# MB_RELAY.net
KiCad netlist of a schematic drawn in Altium Designer
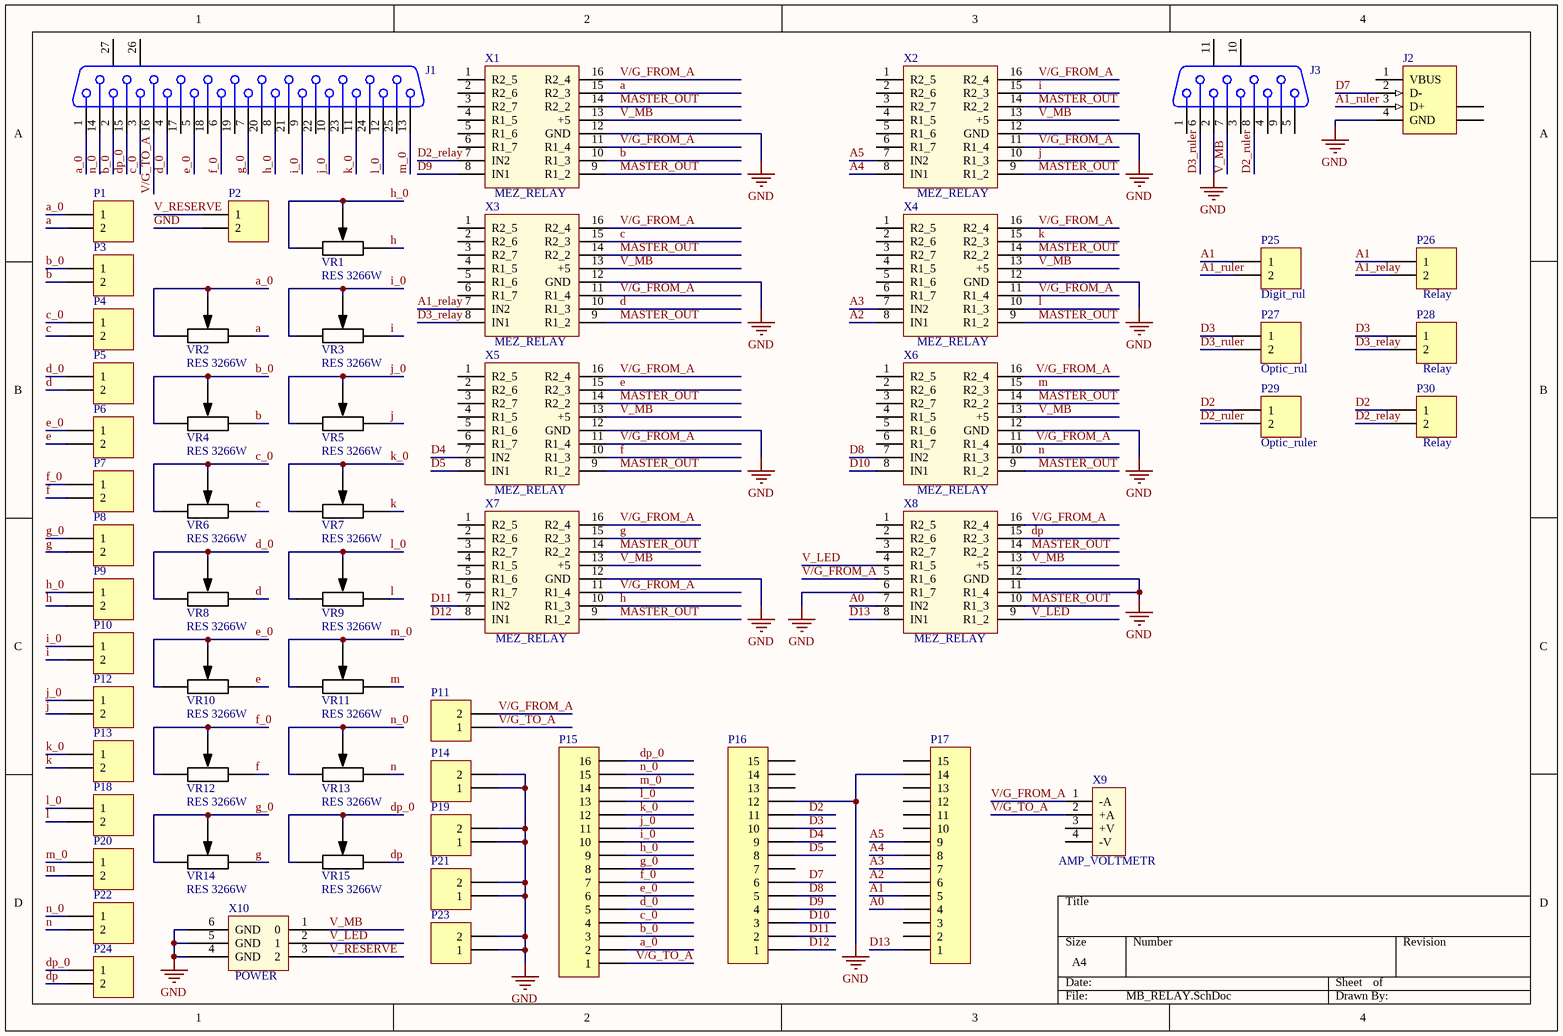
[diagram p0: MB_RELAY.SchDoc]

(export (version "E")
  (design (tool "Eeschema 10.0.6"))
  (components
    (comp (ref "J1")
      (value "D Connector 25")
      (footprint "DSUB1.385-2H25A")
      (description "Receptacle Assembly, 25 Position, Right Angle")
      (fields (field (name "PUBLISHER") "Altium Limited"))
      (libsource (lib "Miscellaneous Connectors") (part "D Connector 25"))
    )
    (comp (ref "J2")
      (value "1-353576-1")
      (footprint "353576")
      (description "USB 1.1, Right Angle, SMT, A Type, Receptacle, 4 Position, White")
      (fields (field (name "PUBLISHER") "Altium Limited"))
      (libsource (lib "AMP Serial Bus USB") (part "1-353576-1"))
    )
    (comp (ref "J3")
      (value "D Connector 9")
      (footprint "DSUB1.385-2H9")
      (description "Receptacle Assembly, 9 Position, Right Angle")
      (fields (field (name "PUBLISHER") "Altium Limited"))
      (libsource (lib "Miscellaneous Connectors") (part "D Connector 9"))
    )
    (comp (ref "P1")
      (value "Header 2")
      (footprint "HDR1X2")
      (description "Header, 2-Pin")
      (fields (field (name "PUBLISHER") "Altium Limited"))
      (libsource (lib "Miscellaneous Connectors") (part "Header 2"))
    )
    (comp (ref "P2")
      (value "Header 2")
      (footprint "HDR1X2")
      (description "Header, 2-Pin")
      (fields (field (name "PUBLISHER") "Altium Limited"))
      (libsource (lib "Miscellaneous Connectors") (part "Header 2"))
    )
    (comp (ref "P3")
      (value "Header 2")
      (footprint "HDR1X2")
      (description "Header, 2-Pin")
      (fields (field (name "PUBLISHER") "Altium Limited"))
      (libsource (lib "Miscellaneous Connectors") (part "Header 2"))
    )
    (comp (ref "P4")
      (value "Header 2")
      (footprint "HDR1X2")
      (description "Header, 2-Pin")
      (fields (field (name "PUBLISHER") "Altium Limited"))
      (libsource (lib "Miscellaneous Connectors") (part "Header 2"))
    )
    (comp (ref "P5")
      (value "Header 2")
      (footprint "HDR1X2")
      (description "Header, 2-Pin")
      (fields (field (name "PUBLISHER") "Altium Limited"))
      (libsource (lib "Miscellaneous Connectors") (part "Header 2"))
    )
    (comp (ref "P6")
      (value "GND")
      (footprint "HDR1X2")
      (description "Header, 2-Pin")
      (fields (field (name "PUBLISHER") "Altium Limited"))
      (libsource (lib "Miscellaneous Connectors") (part "Header 2"))
    )
    (comp (ref "P7")
      (value "GND")
      (footprint "HDR1X2")
      (description "Header, 2-Pin")
      (fields (field (name "PUBLISHER") "Altium Limited"))
      (libsource (lib "Miscellaneous Connectors") (part "Header 2"))
    )
    (comp (ref "P8")
      (value "GND")
      (footprint "HDR1X2")
      (description "Header, 2-Pin")
      (fields (field (name "PUBLISHER") "Altium Limited"))
      (libsource (lib "Miscellaneous Connectors") (part "Header 2"))
    )
    (comp (ref "P9")
      (value "GND")
      (footprint "HDR1X2")
      (description "Header, 2-Pin")
      (fields (field (name "PUBLISHER") "Altium Limited"))
      (libsource (lib "Miscellaneous Connectors") (part "Header 2"))
    )
    (comp (ref "P10")
      (value "Header 2")
      (footprint "HDR1X2")
      (description "Header, 2-Pin")
      (fields (field (name "PUBLISHER") "Altium Limited"))
      (libsource (lib "Miscellaneous Connectors") (part "Header 2"))
    )
    (comp (ref "P11")
      (value "Header 2")
      (footprint "HDR1X2")
      (description "Header, 2-Pin")
      (fields (field (name "PUBLISHER") "Altium Limited"))
      (libsource (lib "") (part "Header 2_1"))
    )
    (comp (ref "P12")
      (value "Header 2")
      (footprint "HDR1X2")
      (description "Header, 2-Pin")
      (fields (field (name "PUBLISHER") "Altium Limited"))
      (libsource (lib "Miscellaneous Connectors") (part "Header 2"))
    )
    (comp (ref "P13")
      (value "GND")
      (footprint "HDR1X2")
      (description "Header, 2-Pin")
      (fields (field (name "PUBLISHER") "Altium Limited"))
      (libsource (lib "Miscellaneous Connectors") (part "Header 2"))
    )
    (comp (ref "P14")
      (value "GND")
      (footprint "HDR1X2")
      (description "Header, 2-Pin")
      (fields (field (name "PUBLISHER") "Altium Limited"))
      (libsource (lib "") (part "Header 2_1"))
    )
    (comp (ref "P15")
      (value "Header 16")
      (footprint "HDR1X16")
      (description "Header, 16-Pin")
      (fields (field (name "PUBLISHER") "Altium Limited"))
      (libsource (lib "Miscellaneous Connectors") (part "Header 16"))
    )
    (comp (ref "P16")
      (value "Header 15")
      (footprint "HDR1X15")
      (description "Header, 15-Pin")
      (fields (field (name "PUBLISHER") "Altium Limited"))
      (libsource (lib "") (part "Header 15_1"))
    )
    (comp (ref "P17")
      (value "Header 15")
      (footprint "HDR1X15")
      (description "Header, 15-Pin")
      (fields (field (name "PUBLISHER") "Altium Limited"))
      (libsource (lib "Miscellaneous Connectors") (part "Header 15"))
    )
    (comp (ref "P18")
      (value "GND")
      (footprint "HDR1X2")
      (description "Header, 2-Pin")
      (fields (field (name "PUBLISHER") "Altium Limited"))
      (libsource (lib "Miscellaneous Connectors") (part "Header 2"))
    )
    (comp (ref "P19")
      (value "GND")
      (footprint "HDR1X2")
      (description "Header, 2-Pin")
      (fields (field (name "PUBLISHER") "Altium Limited"))
      (libsource (lib "") (part "Header 2_1"))
    )
    (comp (ref "P20")
      (value "GND")
      (footprint "HDR1X2")
      (description "Header, 2-Pin")
      (fields (field (name "PUBLISHER") "Altium Limited"))
      (libsource (lib "Miscellaneous Connectors") (part "Header 2"))
    )
    (comp (ref "P21")
      (value "GND")
      (footprint "HDR1X2")
      (description "Header, 2-Pin")
      (fields (field (name "PUBLISHER") "Altium Limited"))
      (libsource (lib "") (part "Header 2_1"))
    )
    (comp (ref "P22")
      (value "GND")
      (footprint "HDR1X2")
      (description "Header, 2-Pin")
      (fields (field (name "PUBLISHER") "Altium Limited"))
      (libsource (lib "Miscellaneous Connectors") (part "Header 2"))
    )
    (comp (ref "P23")
      (value "GND")
      (footprint "HDR1X2")
      (description "Header, 2-Pin")
      (fields (field (name "PUBLISHER") "Altium Limited"))
      (libsource (lib "") (part "Header 2_1"))
    )
    (comp (ref "P24")
      (value "GND")
      (footprint "HDR1X2")
      (description "Header, 2-Pin")
      (fields (field (name "PUBLISHER") "Altium Limited"))
      (libsource (lib "Miscellaneous Connectors") (part "Header 2"))
    )
    (comp (ref "P25")
      (value "Digit_rul")
      (footprint "HDR1X2")
      (description "Header, 2-Pin")
      (fields (field (name "PUBLISHER") "Altium Limited"))
      (libsource (lib "Miscellaneous Connectors") (part "Header 2"))
    )
    (comp (ref "P26")
      (value "Relay")
      (footprint "HDR1X2")
      (description "Header, 2-Pin")
      (fields (field (name "PUBLISHER") "Altium Limited"))
      (libsource (lib "Miscellaneous Connectors") (part "Header 2"))
    )
    (comp (ref "P27")
      (value "Optic_rul")
      (footprint "HDR1X2")
      (description "Header, 2-Pin")
      (fields (field (name "PUBLISHER") "Altium Limited"))
      (libsource (lib "Miscellaneous Connectors") (part "Header 2"))
    )
    (comp (ref "P28")
      (value "Relay")
      (footprint "HDR1X2")
      (description "Header, 2-Pin")
      (fields (field (name "PUBLISHER") "Altium Limited"))
      (libsource (lib "Miscellaneous Connectors") (part "Header 2"))
    )
    (comp (ref "P29")
      (value "Optic_ruler")
      (footprint "HDR1X2")
      (description "Header, 2-Pin")
      (fields (field (name "PUBLISHER") "Altium Limited"))
      (libsource (lib "Miscellaneous Connectors") (part "Header 2"))
    )
    (comp (ref "P30")
      (value "Relay")
      (footprint "HDR1X2")
      (description "Header, 2-Pin")
      (fields (field (name "PUBLISHER") "Altium Limited"))
      (libsource (lib "Miscellaneous Connectors") (part "Header 2"))
    )
    (comp (ref "VR1")
      (value "RES 3266W")
      (footprint "aab_Passive:RES 3266W")
      (libsource (lib "aab_Schlib") (part "RES 3266W"))
    )
    (comp (ref "VR2")
      (value "RES 3266W")
      (footprint "aab_Passive:RES 3266W")
      (libsource (lib "aab_Schlib") (part "RES 3266W"))
    )
    (comp (ref "VR3")
      (value "RES 3266W")
      (footprint "aab_Passive:RES 3266W")
      (libsource (lib "aab_Schlib") (part "RES 3266W"))
    )
    (comp (ref "VR4")
      (value "RES 3266W")
      (footprint "aab_Passive:RES 3266W")
      (libsource (lib "aab_Schlib") (part "RES 3266W"))
    )
    (comp (ref "VR5")
      (value "RES 3266W")
      (footprint "aab_Passive:RES 3266W")
      (libsource (lib "aab_Schlib") (part "RES 3266W"))
    )
    (comp (ref "VR6")
      (value "RES 3266W")
      (footprint "aab_Passive:RES 3266W")
      (libsource (lib "aab_Schlib") (part "RES 3266W"))
    )
    (comp (ref "VR7")
      (value "RES 3266W")
      (footprint "aab_Passive:RES 3266W")
      (libsource (lib "aab_Schlib") (part "RES 3266W"))
    )
    (comp (ref "VR8")
      (value "RES 3266W")
      (footprint "aab_Passive:RES 3266W")
      (libsource (lib "aab_Schlib") (part "RES 3266W"))
    )
    (comp (ref "VR9")
      (value "RES 3266W")
      (footprint "aab_Passive:RES 3266W")
      (libsource (lib "aab_Schlib") (part "RES 3266W"))
    )
    (comp (ref "VR10")
      (value "RES 3266W")
      (footprint "aab_Passive:RES 3266W")
      (libsource (lib "aab_Schlib") (part "RES 3266W"))
    )
    (comp (ref "VR11")
      (value "RES 3266W")
      (footprint "aab_Passive:RES 3266W")
      (libsource (lib "aab_Schlib") (part "RES 3266W"))
    )
    (comp (ref "VR12")
      (value "RES 3266W")
      (footprint "aab_Passive:RES 3266W")
      (libsource (lib "aab_Schlib") (part "RES 3266W"))
    )
    (comp (ref "VR13")
      (value "RES 3266W")
      (footprint "aab_Passive:RES 3266W")
      (libsource (lib "aab_Schlib") (part "RES 3266W"))
    )
    (comp (ref "VR14")
      (value "RES 3266W")
      (footprint "aab_Passive:RES 3266W")
      (libsource (lib "aab_Schlib") (part "RES 3266W"))
    )
    (comp (ref "VR15")
      (value "RES 3266W")
      (footprint "aab_Passive:RES 3266W")
      (libsource (lib "aab_Schlib") (part "RES 3266W"))
    )
    (comp (ref "X1")
      (value "MEZ_RELAY")
      (footprint "MEZ_RELAY")
      (libsource (lib "msp_SchLib") (part "MEZ_RELAY"))
    )
    (comp (ref "X2")
      (value "MEZ_RELAY")
      (footprint "MEZ_RELAY")
      (libsource (lib "msp_SchLib") (part "MEZ_RELAY"))
    )
    (comp (ref "X3")
      (value "MEZ_RELAY")
      (footprint "MEZ_RELAY")
      (libsource (lib "msp_SchLib") (part "MEZ_RELAY"))
    )
    (comp (ref "X4")
      (value "MEZ_RELAY")
      (footprint "MEZ_RELAY")
      (libsource (lib "msp_SchLib") (part "MEZ_RELAY"))
    )
    (comp (ref "X5")
      (value "MEZ_RELAY")
      (footprint "MEZ_RELAY")
      (libsource (lib "msp_SchLib") (part "MEZ_RELAY"))
    )
    (comp (ref "X6")
      (value "MEZ_RELAY")
      (footprint "MEZ_RELAY")
      (libsource (lib "msp_SchLib") (part "MEZ_RELAY"))
    )
    (comp (ref "X7")
      (value "MEZ_RELAY")
      (footprint "MEZ_RELAY")
      (libsource (lib "msp_SchLib") (part "MEZ_RELAY"))
    )
    (comp (ref "X8")
      (value "MEZ_RELAY")
      (footprint "MEZ_RELAY")
      (libsource (lib "msp_SchLib") (part "MEZ_RELAY"))
    )
    (comp (ref "X9")
      (value "AMP_VOLTMETR")
      (footprint "vpl_Passive:AMP_VOLTMETER")
      (libsource (lib "msp_SchLib") (part "AMP_VOLTMETR"))
    )
    (comp (ref "X10")
      (value "POWER")
      (footprint "vpl_Passive:POWER")
      (libsource (lib "msp_SchLib") (part "POWER"))
    )
  )
  (nets
    (net (code "1") (name "/A0") (class "Default")
      (node (ref "P17") (pin "4") (pinfunction "4_4") (pintype "passive"))
      (node (ref "X8") (pin "7") (pinfunction "IN2_7") (pintype "passive"))
    )
    (net (code "2") (name "/A1") (class "Default")
      (node (ref "P17") (pin "5") (pinfunction "5_5") (pintype "passive"))
      (node (ref "P25") (pin "1") (pinfunction "1_1") (pintype "passive"))
      (node (ref "P26") (pin "1") (pinfunction "1_1") (pintype "passive"))
    )
    (net (code "3") (name "/A1_relay") (class "Default")
      (node (ref "P26") (pin "2") (pinfunction "2_2") (pintype "passive"))
      (node (ref "X3") (pin "7") (pinfunction "IN2_7") (pintype "passive"))
    )
    (net (code "4") (name "/A1_ruler") (class "Default")
      (node (ref "J2") (pin "3") (pinfunction "D+_3") (pintype "input"))
      (node (ref "P25") (pin "2") (pinfunction "2_2") (pintype "passive"))
    )
    (net (code "5") (name "/A2") (class "Default")
      (node (ref "P17") (pin "6") (pinfunction "6_6") (pintype "passive"))
      (node (ref "X4") (pin "8") (pinfunction "IN1_8") (pintype "passive"))
    )
    (net (code "6") (name "/A3") (class "Default")
      (node (ref "P17") (pin "7") (pinfunction "7_7") (pintype "passive"))
      (node (ref "X4") (pin "7") (pinfunction "IN2_7") (pintype "passive"))
    )
    (net (code "7") (name "/A4") (class "Default")
      (node (ref "P17") (pin "8") (pinfunction "8_8") (pintype "passive"))
      (node (ref "X2") (pin "8") (pinfunction "IN1_8") (pintype "passive"))
    )
    (net (code "8") (name "/A5") (class "Default")
      (node (ref "P17") (pin "9") (pinfunction "9_9") (pintype "passive"))
      (node (ref "X2") (pin "7") (pinfunction "IN2_7") (pintype "passive"))
    )
    (net (code "9") (name "/D2") (class "Default")
      (node (ref "P16") (pin "11") (pinfunction "11_11") (pintype "passive"))
      (node (ref "P29") (pin "1") (pinfunction "1_1") (pintype "passive"))
      (node (ref "P30") (pin "1") (pinfunction "1_1") (pintype "passive"))
    )
    (net (code "10") (name "/D2_relay") (class "Default")
      (node (ref "P30") (pin "2") (pinfunction "2_2") (pintype "passive"))
      (node (ref "X1") (pin "7") (pinfunction "IN2_7") (pintype "passive"))
    )
    (net (code "11") (name "/D2_ruler") (class "Default")
      (node (ref "J3") (pin "8") (pinfunction "8_8") (pintype "passive"))
      (node (ref "P29") (pin "2") (pinfunction "2_2") (pintype "passive"))
    )
    (net (code "12") (name "/D3") (class "Default")
      (node (ref "P16") (pin "10") (pinfunction "10_10") (pintype "passive"))
      (node (ref "P27") (pin "1") (pinfunction "1_1") (pintype "passive"))
      (node (ref "P28") (pin "1") (pinfunction "1_1") (pintype "passive"))
    )
    (net (code "13") (name "/D3_relay") (class "Default")
      (node (ref "P28") (pin "2") (pinfunction "2_2") (pintype "passive"))
      (node (ref "X3") (pin "8") (pinfunction "IN1_8") (pintype "passive"))
    )
    (net (code "14") (name "/D3_ruler") (class "Default")
      (node (ref "J3") (pin "6") (pinfunction "6_6") (pintype "passive"))
      (node (ref "P27") (pin "2") (pinfunction "2_2") (pintype "passive"))
    )
    (net (code "15") (name "/D4") (class "Default")
      (node (ref "P16") (pin "9") (pinfunction "9_9") (pintype "passive"))
      (node (ref "X5") (pin "7") (pinfunction "IN2_7") (pintype "passive"))
    )
    (net (code "16") (name "/D5") (class "Default")
      (node (ref "P16") (pin "8") (pinfunction "8_8") (pintype "passive"))
      (node (ref "X5") (pin "8") (pinfunction "IN1_8") (pintype "passive"))
    )
    (net (code "17") (name "/D7") (class "Default")
      (node (ref "J2") (pin "2") (pinfunction "D-_2") (pintype "input"))
      (node (ref "P16") (pin "6") (pinfunction "6_6") (pintype "passive"))
    )
    (net (code "18") (name "/D8") (class "Default")
      (node (ref "P16") (pin "5") (pinfunction "5_5") (pintype "passive"))
      (node (ref "X6") (pin "7") (pinfunction "IN2_7") (pintype "passive"))
    )
    (net (code "19") (name "/D9") (class "Default")
      (node (ref "P16") (pin "4") (pinfunction "4_4") (pintype "passive"))
      (node (ref "X1") (pin "8") (pinfunction "IN1_8") (pintype "passive"))
    )
    (net (code "20") (name "/D10") (class "Default")
      (node (ref "P16") (pin "3") (pinfunction "3_3") (pintype "passive"))
      (node (ref "X6") (pin "8") (pinfunction "IN1_8") (pintype "passive"))
    )
    (net (code "21") (name "/D11") (class "Default")
      (node (ref "P16") (pin "2") (pinfunction "2_2") (pintype "passive"))
      (node (ref "X7") (pin "7") (pinfunction "IN2_7") (pintype "passive"))
    )
    (net (code "22") (name "/D12") (class "Default")
      (node (ref "P16") (pin "1") (pinfunction "1_1") (pintype "passive"))
      (node (ref "X7") (pin "8") (pinfunction "IN1_8") (pintype "passive"))
    )
    (net (code "23") (name "/D13") (class "Default")
      (node (ref "P17") (pin "1") (pinfunction "1_1") (pintype "passive"))
      (node (ref "X8") (pin "8") (pinfunction "IN1_8") (pintype "passive"))
    )
    (net (code "24") (name "/MASTER_OUT") (class "Default")
      (node (ref "X1") (pin "14") (pinfunction "R2_2_14") (pintype "passive"))
      (node (ref "X1") (pin "9") (pinfunction "R1_2_9") (pintype "passive"))
      (node (ref "X2") (pin "14") (pinfunction "R2_2_14") (pintype "passive"))
      (node (ref "X2") (pin "9") (pinfunction "R1_2_9") (pintype "passive"))
      (node (ref "X3") (pin "14") (pinfunction "R2_2_14") (pintype "passive"))
      (node (ref "X3") (pin "9") (pinfunction "R1_2_9") (pintype "passive"))
      (node (ref "X4") (pin "14") (pinfunction "R2_2_14") (pintype "passive"))
      (node (ref "X4") (pin "9") (pinfunction "R1_2_9") (pintype "passive"))
      (node (ref "X5") (pin "14") (pinfunction "R2_2_14") (pintype "passive"))
      (node (ref "X5") (pin "9") (pinfunction "R1_2_9") (pintype "passive"))
      (node (ref "X6") (pin "14") (pinfunction "R2_2_14") (pintype "passive"))
      (node (ref "X6") (pin "9") (pinfunction "R1_2_9") (pintype "passive"))
      (node (ref "X7") (pin "14") (pinfunction "R2_2_14") (pintype "passive"))
      (node (ref "X7") (pin "9") (pinfunction "R1_2_9") (pintype "passive"))
      (node (ref "X8") (pin "10") (pinfunction "R1_3_10") (pintype "passive"))
      (node (ref "X8") (pin "14") (pinfunction "R2_2_14") (pintype "passive"))
    )
    (net (code "25") (name "/V_LED") (class "Default")
      (node (ref "X10") (pin "2") (pinfunction "1_2") (pintype "passive"))
      (node (ref "X8") (pin "4") (pinfunction "R1_5_4") (pintype "passive"))
      (node (ref "X8") (pin "9") (pinfunction "R1_2_9") (pintype "passive"))
    )
    (net (code "26") (name "/V_MB") (class "Default")
      (node (ref "J3") (pin "7") (pinfunction "7_7") (pintype "passive"))
      (node (ref "X1") (pin "13") (pinfunction "+5_13") (pintype "passive"))
      (node (ref "X10") (pin "1") (pinfunction "0_1") (pintype "passive"))
      (node (ref "X2") (pin "13") (pinfunction "+5_13") (pintype "passive"))
      (node (ref "X3") (pin "13") (pinfunction "+5_13") (pintype "passive"))
      (node (ref "X4") (pin "13") (pinfunction "+5_13") (pintype "passive"))
      (node (ref "X5") (pin "13") (pinfunction "+5_13") (pintype "passive"))
      (node (ref "X6") (pin "13") (pinfunction "+5_13") (pintype "passive"))
      (node (ref "X7") (pin "13") (pinfunction "+5_13") (pintype "passive"))
      (node (ref "X8") (pin "13") (pinfunction "+5_13") (pintype "passive"))
    )
    (net (code "27") (name "/V_RESERVE") (class "Default")
      (node (ref "P2") (pin "1") (pinfunction "1_1") (pintype "passive"))
      (node (ref "X10") (pin "3") (pinfunction "2_3") (pintype "passive"))
    )
    (net (code "28") (name "/V{slash}G_FROM_A") (class "Default")
      (node (ref "P11") (pin "2") (pinfunction "2_2") (pintype "passive"))
      (node (ref "X1") (pin "11") (pinfunction "R1_4_11") (pintype "passive"))
      (node (ref "X1") (pin "16") (pinfunction "R2_4_16") (pintype "passive"))
      (node (ref "X2") (pin "11") (pinfunction "R1_4_11") (pintype "passive"))
      (node (ref "X2") (pin "16") (pinfunction "R2_4_16") (pintype "passive"))
      (node (ref "X3") (pin "11") (pinfunction "R1_4_11") (pintype "passive"))
      (node (ref "X3") (pin "16") (pinfunction "R2_4_16") (pintype "passive"))
      (node (ref "X4") (pin "11") (pinfunction "R1_4_11") (pintype "passive"))
      (node (ref "X4") (pin "16") (pinfunction "R2_4_16") (pintype "passive"))
      (node (ref "X5") (pin "11") (pinfunction "R1_4_11") (pintype "passive"))
      (node (ref "X5") (pin "16") (pinfunction "R2_4_16") (pintype "passive"))
      (node (ref "X6") (pin "11") (pinfunction "R1_4_11") (pintype "passive"))
      (node (ref "X6") (pin "16") (pinfunction "R2_4_16") (pintype "passive"))
      (node (ref "X7") (pin "11") (pinfunction "R1_4_11") (pintype "passive"))
      (node (ref "X7") (pin "16") (pinfunction "R2_4_16") (pintype "passive"))
      (node (ref "X8") (pin "16") (pinfunction "R2_4_16") (pintype "passive"))
      (node (ref "X8") (pin "5") (pinfunction "R1_6_5") (pintype "passive"))
      (node (ref "X9") (pin "1") (pinfunction "-A_1") (pintype "passive"))
    )
    (net (code "29") (name "/V{slash}G_TO_A") (class "Default")
      (node (ref "J1") (pin "16") (pinfunction "16_16") (pintype "passive"))
      (node (ref "P11") (pin "1") (pinfunction "1_1") (pintype "passive"))
      (node (ref "P15") (pin "1") (pinfunction "1_1") (pintype "passive"))
      (node (ref "X9") (pin "2") (pinfunction "+A_2") (pintype "passive"))
    )
    (net (code "30") (name "/a") (class "Default")
      (node (ref "P1") (pin "2") (pinfunction "2_2") (pintype "passive"))
      (node (ref "VR2") (pin "3") (pinfunction "3_3") (pintype "passive"))
      (node (ref "X1") (pin "15") (pinfunction "R2_3_15") (pintype "passive"))
    )
    (net (code "31") (name "/a_0") (class "Default")
      (node (ref "J1") (pin "1") (pinfunction "1_1") (pintype "passive"))
      (node (ref "P1") (pin "1") (pinfunction "1_1") (pintype "passive"))
      (node (ref "P15") (pin "2") (pinfunction "2_2") (pintype "passive"))
      (node (ref "VR2") (pin "1") (pinfunction "1_1") (pintype "passive"))
      (node (ref "VR2") (pin "2") (pinfunction "2_2") (pintype "passive"))
    )
    (net (code "32") (name "/b") (class "Default")
      (node (ref "P3") (pin "2") (pinfunction "2_2") (pintype "passive"))
      (node (ref "VR4") (pin "3") (pinfunction "3_3") (pintype "passive"))
      (node (ref "X1") (pin "10") (pinfunction "R1_3_10") (pintype "passive"))
    )
    (net (code "33") (name "/b_0") (class "Default")
      (node (ref "J1") (pin "2") (pinfunction "2_2") (pintype "passive"))
      (node (ref "P15") (pin "3") (pinfunction "3_3") (pintype "passive"))
      (node (ref "P3") (pin "1") (pinfunction "1_1") (pintype "passive"))
      (node (ref "VR4") (pin "1") (pinfunction "1_1") (pintype "passive"))
      (node (ref "VR4") (pin "2") (pinfunction "2_2") (pintype "passive"))
    )
    (net (code "34") (name "/c") (class "Default")
      (node (ref "P4") (pin "2") (pinfunction "2_2") (pintype "passive"))
      (node (ref "VR6") (pin "3") (pinfunction "3_3") (pintype "passive"))
      (node (ref "X3") (pin "15") (pinfunction "R2_3_15") (pintype "passive"))
    )
    (net (code "35") (name "/c_0") (class "Default")
      (node (ref "J1") (pin "3") (pinfunction "3_3") (pintype "passive"))
      (node (ref "P15") (pin "4") (pinfunction "4_4") (pintype "passive"))
      (node (ref "P4") (pin "1") (pinfunction "1_1") (pintype "passive"))
      (node (ref "VR6") (pin "1") (pinfunction "1_1") (pintype "passive"))
      (node (ref "VR6") (pin "2") (pinfunction "2_2") (pintype "passive"))
    )
    (net (code "36") (name "/d") (class "Default")
      (node (ref "P5") (pin "2") (pinfunction "2_2") (pintype "passive"))
      (node (ref "VR8") (pin "3") (pinfunction "3_3") (pintype "passive"))
      (node (ref "X3") (pin "10") (pinfunction "R1_3_10") (pintype "passive"))
    )
    (net (code "37") (name "/d_0") (class "Default")
      (node (ref "J1") (pin "4") (pinfunction "4_4") (pintype "passive"))
      (node (ref "P15") (pin "5") (pinfunction "5_5") (pintype "passive"))
      (node (ref "P5") (pin "1") (pinfunction "1_1") (pintype "passive"))
      (node (ref "VR8") (pin "1") (pinfunction "1_1") (pintype "passive"))
      (node (ref "VR8") (pin "2") (pinfunction "2_2") (pintype "passive"))
    )
    (net (code "38") (name "/dp") (class "Default")
      (node (ref "P24") (pin "2") (pinfunction "2_2") (pintype "passive"))
      (node (ref "VR15") (pin "3") (pinfunction "3_3") (pintype "passive"))
      (node (ref "X8") (pin "15") (pinfunction "R2_3_15") (pintype "passive"))
    )
    (net (code "39") (name "/dp_0") (class "Default")
      (node (ref "J1") (pin "15") (pinfunction "15_15") (pintype "passive"))
      (node (ref "P15") (pin "16") (pinfunction "16_16") (pintype "passive"))
      (node (ref "P24") (pin "1") (pinfunction "1_1") (pintype "passive"))
      (node (ref "VR15") (pin "1") (pinfunction "1_1") (pintype "passive"))
      (node (ref "VR15") (pin "2") (pinfunction "2_2") (pintype "passive"))
    )
    (net (code "40") (name "/e") (class "Default")
      (node (ref "P6") (pin "2") (pinfunction "2_2") (pintype "passive"))
      (node (ref "VR10") (pin "3") (pinfunction "3_3") (pintype "passive"))
      (node (ref "X5") (pin "15") (pinfunction "R2_3_15") (pintype "passive"))
    )
    (net (code "41") (name "/e_0") (class "Default")
      (node (ref "J1") (pin "5") (pinfunction "5_5") (pintype "passive"))
      (node (ref "P15") (pin "6") (pinfunction "6_6") (pintype "passive"))
      (node (ref "P6") (pin "1") (pinfunction "1_1") (pintype "passive"))
      (node (ref "VR10") (pin "1") (pinfunction "1_1") (pintype "passive"))
      (node (ref "VR10") (pin "2") (pinfunction "2_2") (pintype "passive"))
    )
    (net (code "42") (name "/f") (class "Default")
      (node (ref "P7") (pin "2") (pinfunction "2_2") (pintype "passive"))
      (node (ref "VR12") (pin "3") (pinfunction "3_3") (pintype "passive"))
      (node (ref "X5") (pin "10") (pinfunction "R1_3_10") (pintype "passive"))
    )
    (net (code "43") (name "/f_0") (class "Default")
      (node (ref "J1") (pin "6") (pinfunction "6_6") (pintype "passive"))
      (node (ref "P15") (pin "7") (pinfunction "7_7") (pintype "passive"))
      (node (ref "P7") (pin "1") (pinfunction "1_1") (pintype "passive"))
      (node (ref "VR12") (pin "1") (pinfunction "1_1") (pintype "passive"))
      (node (ref "VR12") (pin "2") (pinfunction "2_2") (pintype "passive"))
    )
    (net (code "44") (name "/g") (class "Default")
      (node (ref "P8") (pin "2") (pinfunction "2_2") (pintype "passive"))
      (node (ref "VR14") (pin "3") (pinfunction "3_3") (pintype "passive"))
      (node (ref "X7") (pin "15") (pinfunction "R2_3_15") (pintype "passive"))
    )
    (net (code "45") (name "/g_0") (class "Default")
      (node (ref "J1") (pin "7") (pinfunction "7_7") (pintype "passive"))
      (node (ref "P15") (pin "8") (pinfunction "8_8") (pintype "passive"))
      (node (ref "P8") (pin "1") (pinfunction "1_1") (pintype "passive"))
      (node (ref "VR14") (pin "1") (pinfunction "1_1") (pintype "passive"))
      (node (ref "VR14") (pin "2") (pinfunction "2_2") (pintype "passive"))
    )
    (net (code "46") (name "/h") (class "Default")
      (node (ref "P9") (pin "2") (pinfunction "2_2") (pintype "passive"))
      (node (ref "VR1") (pin "3") (pinfunction "3_3") (pintype "passive"))
      (node (ref "X7") (pin "10") (pinfunction "R1_3_10") (pintype "passive"))
    )
    (net (code "47") (name "/h_0") (class "Default")
      (node (ref "J1") (pin "8") (pinfunction "8_8") (pintype "passive"))
      (node (ref "P15") (pin "9") (pinfunction "9_9") (pintype "passive"))
      (node (ref "P9") (pin "1") (pinfunction "1_1") (pintype "passive"))
      (node (ref "VR1") (pin "1") (pinfunction "1_1") (pintype "passive"))
      (node (ref "VR1") (pin "2") (pinfunction "2_2") (pintype "passive"))
    )
    (net (code "48") (name "/i") (class "Default")
      (node (ref "P10") (pin "2") (pinfunction "2_2") (pintype "passive"))
      (node (ref "VR3") (pin "3") (pinfunction "3_3") (pintype "passive"))
      (node (ref "X2") (pin "15") (pinfunction "R2_3_15") (pintype "passive"))
    )
    (net (code "49") (name "/i_0") (class "Default")
      (node (ref "J1") (pin "9") (pinfunction "9_9") (pintype "passive"))
      (node (ref "P10") (pin "1") (pinfunction "1_1") (pintype "passive"))
      (node (ref "P15") (pin "10") (pinfunction "10_10") (pintype "passive"))
      (node (ref "VR3") (pin "1") (pinfunction "1_1") (pintype "passive"))
      (node (ref "VR3") (pin "2") (pinfunction "2_2") (pintype "passive"))
    )
    (net (code "50") (name "/j") (class "Default")
      (node (ref "P12") (pin "2") (pinfunction "2_2") (pintype "passive"))
      (node (ref "VR5") (pin "3") (pinfunction "3_3") (pintype "passive"))
      (node (ref "X2") (pin "10") (pinfunction "R1_3_10") (pintype "passive"))
    )
    (net (code "51") (name "/j_0") (class "Default")
      (node (ref "J1") (pin "10") (pinfunction "10_10") (pintype "passive"))
      (node (ref "P12") (pin "1") (pinfunction "1_1") (pintype "passive"))
      (node (ref "P15") (pin "11") (pinfunction "11_11") (pintype "passive"))
      (node (ref "VR5") (pin "1") (pinfunction "1_1") (pintype "passive"))
      (node (ref "VR5") (pin "2") (pinfunction "2_2") (pintype "passive"))
    )
    (net (code "52") (name "/k") (class "Default")
      (node (ref "P13") (pin "2") (pinfunction "2_2") (pintype "passive"))
      (node (ref "VR7") (pin "3") (pinfunction "3_3") (pintype "passive"))
      (node (ref "X4") (pin "15") (pinfunction "R2_3_15") (pintype "passive"))
    )
    (net (code "53") (name "/k_0") (class "Default")
      (node (ref "J1") (pin "11") (pinfunction "11_11") (pintype "passive"))
      (node (ref "P13") (pin "1") (pinfunction "1_1") (pintype "passive"))
      (node (ref "P15") (pin "12") (pinfunction "12_12") (pintype "passive"))
      (node (ref "VR7") (pin "1") (pinfunction "1_1") (pintype "passive"))
      (node (ref "VR7") (pin "2") (pinfunction "2_2") (pintype "passive"))
    )
    (net (code "54") (name "/l") (class "Default")
      (node (ref "P18") (pin "2") (pinfunction "2_2") (pintype "passive"))
      (node (ref "VR9") (pin "3") (pinfunction "3_3") (pintype "passive"))
      (node (ref "X4") (pin "10") (pinfunction "R1_3_10") (pintype "passive"))
    )
    (net (code "55") (name "/l_0") (class "Default")
      (node (ref "J1") (pin "12") (pinfunction "12_12") (pintype "passive"))
      (node (ref "P15") (pin "13") (pinfunction "13_13") (pintype "passive"))
      (node (ref "P18") (pin "1") (pinfunction "1_1") (pintype "passive"))
      (node (ref "VR9") (pin "1") (pinfunction "1_1") (pintype "passive"))
      (node (ref "VR9") (pin "2") (pinfunction "2_2") (pintype "passive"))
    )
    (net (code "56") (name "/m") (class "Default")
      (node (ref "P20") (pin "2") (pinfunction "2_2") (pintype "passive"))
      (node (ref "VR11") (pin "3") (pinfunction "3_3") (pintype "passive"))
      (node (ref "X6") (pin "15") (pinfunction "R2_3_15") (pintype "passive"))
    )
    (net (code "57") (name "/m_0") (class "Default")
      (node (ref "J1") (pin "13") (pinfunction "13_13") (pintype "passive"))
      (node (ref "P15") (pin "14") (pinfunction "14_14") (pintype "passive"))
      (node (ref "P20") (pin "1") (pinfunction "1_1") (pintype "passive"))
      (node (ref "VR11") (pin "1") (pinfunction "1_1") (pintype "passive"))
      (node (ref "VR11") (pin "2") (pinfunction "2_2") (pintype "passive"))
    )
    (net (code "58") (name "/n") (class "Default")
      (node (ref "P22") (pin "2") (pinfunction "2_2") (pintype "passive"))
      (node (ref "VR13") (pin "3") (pinfunction "3_3") (pintype "passive"))
      (node (ref "X6") (pin "10") (pinfunction "R1_3_10") (pintype "passive"))
    )
    (net (code "59") (name "/n_0") (class "Default")
      (node (ref "J1") (pin "14") (pinfunction "14_14") (pintype "passive"))
      (node (ref "P15") (pin "15") (pinfunction "15_15") (pintype "passive"))
      (node (ref "P22") (pin "1") (pinfunction "1_1") (pintype "passive"))
      (node (ref "VR13") (pin "1") (pinfunction "1_1") (pintype "passive"))
      (node (ref "VR13") (pin "2") (pinfunction "2_2") (pintype "passive"))
    )
    (net (code "60") (name "GND") (class "Default")
      (node (ref "J2") (pin "4") (pinfunction "GND_4") (pintype "power_in"))
      (node (ref "J3") (pin "2") (pinfunction "2_2") (pintype "passive"))
      (node (ref "P14") (pin "1") (pinfunction "1_1") (pintype "passive"))
      (node (ref "P14") (pin "2") (pinfunction "2_2") (pintype "passive"))
      (node (ref "P16") (pin "12") (pinfunction "12_12") (pintype "passive"))
      (node (ref "P17") (pin "14") (pinfunction "14_14") (pintype "passive"))
      (node (ref "P19") (pin "1") (pinfunction "1_1") (pintype "passive"))
      (node (ref "P19") (pin "2") (pinfunction "2_2") (pintype "passive"))
      (node (ref "P2") (pin "2") (pinfunction "2_2") (pintype "passive"))
      (node (ref "P21") (pin "1") (pinfunction "1_1") (pintype "passive"))
      (node (ref "P21") (pin "2") (pinfunction "2_2") (pintype "passive"))
      (node (ref "P23") (pin "1") (pinfunction "1_1") (pintype "passive"))
      (node (ref "P23") (pin "2") (pinfunction "2_2") (pintype "passive"))
      (node (ref "X1") (pin "12") (pinfunction "GND_12") (pintype "passive"))
      (node (ref "X10") (pin "4") (pinfunction "GND_4") (pintype "passive"))
      (node (ref "X10") (pin "5") (pinfunction "GND_5") (pintype "passive"))
      (node (ref "X10") (pin "6") (pinfunction "GND_6") (pintype "passive"))
      (node (ref "X2") (pin "12") (pinfunction "GND_12") (pintype "passive"))
      (node (ref "X3") (pin "12") (pinfunction "GND_12") (pintype "passive"))
      (node (ref "X4") (pin "12") (pinfunction "GND_12") (pintype "passive"))
      (node (ref "X5") (pin "12") (pinfunction "GND_12") (pintype "passive"))
      (node (ref "X6") (pin "12") (pinfunction "GND_12") (pintype "passive"))
      (node (ref "X7") (pin "12") (pinfunction "GND_12") (pintype "passive"))
      (node (ref "X8") (pin "11") (pinfunction "R1_4_11") (pintype "passive"))
      (node (ref "X8") (pin "12") (pinfunction "GND_12") (pintype "passive"))
      (node (ref "X8") (pin "6") (pinfunction "R1_7_6") (pintype "passive"))
    )
    (net (code "61") (name "unconnected-(J1-MH1-Pad26)") (class "Default")
      (node (ref "J1") (pin "26") (pinfunction "MH1_26") (pintype "passive"))
    )
    (net (code "62") (name "unconnected-(J1-MH2-Pad27)") (class "Default")
      (node (ref "J1") (pin "27") (pinfunction "MH2_27") (pintype "passive"))
    )
    (net (code "63") (name "unconnected-(J1-Pad17)") (class "Default")
      (node (ref "J1") (pin "17") (pinfunction "17_17") (pintype "passive"))
    )
    (net (code "64") (name "unconnected-(J1-Pad18)") (class "Default")
      (node (ref "J1") (pin "18") (pinfunction "18_18") (pintype "passive"))
    )
    (net (code "65") (name "unconnected-(J1-Pad19)") (class "Default")
      (node (ref "J1") (pin "19") (pinfunction "19_19") (pintype "passive"))
    )
    (net (code "66") (name "unconnected-(J1-Pad20)") (class "Default")
      (node (ref "J1") (pin "20") (pinfunction "20_20") (pintype "passive"))
    )
    (net (code "67") (name "unconnected-(J1-Pad21)") (class "Default")
      (node (ref "J1") (pin "21") (pinfunction "21_21") (pintype "passive"))
    )
    (net (code "68") (name "unconnected-(J1-Pad22)") (class "Default")
      (node (ref "J1") (pin "22") (pinfunction "22_22") (pintype "passive"))
    )
    (net (code "69") (name "unconnected-(J1-Pad23)") (class "Default")
      (node (ref "J1") (pin "23") (pinfunction "23_23") (pintype "passive"))
    )
    (net (code "70") (name "unconnected-(J1-Pad24)") (class "Default")
      (node (ref "J1") (pin "24") (pinfunction "24_24") (pintype "passive"))
    )
    (net (code "71") (name "unconnected-(J1-Pad25)") (class "Default")
      (node (ref "J1") (pin "25") (pinfunction "25_25") (pintype "passive"))
    )
    (net (code "72") (name "unconnected-(J2-SHLD-Pad5)") (class "Default")
      (node (ref "J2") (pin "5") (pinfunction "SHLD_5") (pintype "passive"))
    )
    (net (code "73") (name "unconnected-(J2-SHLD-Pad6)") (class "Default")
      (node (ref "J2") (pin "6") (pinfunction "SHLD_6") (pintype "passive"))
    )
    (net (code "74") (name "unconnected-(J2-VBUS-Pad1)") (class "Default")
      (node (ref "J2") (pin "1") (pinfunction "VBUS_1") (pintype "power_in"))
    )
    (net (code "75") (name "unconnected-(J3-MH1-Pad10)") (class "Default")
      (node (ref "J3") (pin "10") (pinfunction "MH1_10") (pintype "passive"))
    )
    (net (code "76") (name "unconnected-(J3-MH2-Pad11)") (class "Default")
      (node (ref "J3") (pin "11") (pinfunction "MH2_11") (pintype "passive"))
    )
    (net (code "77") (name "unconnected-(J3-Pad1)") (class "Default")
      (node (ref "J3") (pin "1") (pinfunction "1_1") (pintype "passive"))
    )
    (net (code "78") (name "unconnected-(J3-Pad3)") (class "Default")
      (node (ref "J3") (pin "3") (pinfunction "3_3") (pintype "passive"))
    )
    (net (code "79") (name "unconnected-(J3-Pad4)") (class "Default")
      (node (ref "J3") (pin "4") (pinfunction "4_4") (pintype "passive"))
    )
    (net (code "80") (name "unconnected-(J3-Pad5)") (class "Default")
      (node (ref "J3") (pin "5") (pinfunction "5_5") (pintype "passive"))
    )
    (net (code "81") (name "unconnected-(J3-Pad9)") (class "Default")
      (node (ref "J3") (pin "9") (pinfunction "9_9") (pintype "passive"))
    )
    (net (code "82") (name "unconnected-(P16-Pad7)") (class "Default")
      (node (ref "P16") (pin "7") (pinfunction "7_7") (pintype "passive"))
    )
    (net (code "83") (name "unconnected-(P16-Pad13)") (class "Default")
      (node (ref "P16") (pin "13") (pinfunction "13_13") (pintype "passive"))
    )
    (net (code "84") (name "unconnected-(P16-Pad14)") (class "Default")
      (node (ref "P16") (pin "14") (pinfunction "14_14") (pintype "passive"))
    )
    (net (code "85") (name "unconnected-(P16-Pad15)") (class "Default")
      (node (ref "P16") (pin "15") (pinfunction "15_15") (pintype "passive"))
    )
    (net (code "86") (name "unconnected-(P17-Pad2)") (class "Default")
      (node (ref "P17") (pin "2") (pinfunction "2_2") (pintype "passive"))
    )
    (net (code "87") (name "unconnected-(P17-Pad3)") (class "Default")
      (node (ref "P17") (pin "3") (pinfunction "3_3") (pintype "passive"))
    )
    (net (code "88") (name "unconnected-(P17-Pad10)") (class "Default")
      (node (ref "P17") (pin "10") (pinfunction "10_10") (pintype "passive"))
    )
    (net (code "89") (name "unconnected-(P17-Pad11)") (class "Default")
      (node (ref "P17") (pin "11") (pinfunction "11_11") (pintype "passive"))
    )
    (net (code "90") (name "unconnected-(P17-Pad12)") (class "Default")
      (node (ref "P17") (pin "12") (pinfunction "12_12") (pintype "passive"))
    )
    (net (code "91") (name "unconnected-(P17-Pad13)") (class "Default")
      (node (ref "P17") (pin "13") (pinfunction "13_13") (pintype "passive"))
    )
    (net (code "92") (name "unconnected-(P17-Pad15)") (class "Default")
      (node (ref "P17") (pin "15") (pinfunction "15_15") (pintype "passive"))
    )
    (net (code "93") (name "unconnected-(X1-R1_5-Pad4)") (class "Default")
      (node (ref "X1") (pin "4") (pinfunction "R1_5_4") (pintype "passive"))
    )
    (net (code "94") (name "unconnected-(X1-R1_6-Pad5)") (class "Default")
      (node (ref "X1") (pin "5") (pinfunction "R1_6_5") (pintype "passive"))
    )
    (net (code "95") (name "unconnected-(X1-R1_7-Pad6)") (class "Default")
      (node (ref "X1") (pin "6") (pinfunction "R1_7_6") (pintype "passive"))
    )
    (net (code "96") (name "unconnected-(X1-R2_5-Pad1)") (class "Default")
      (node (ref "X1") (pin "1") (pinfunction "R2_5_1") (pintype "passive"))
    )
    (net (code "97") (name "unconnected-(X1-R2_6-Pad2)") (class "Default")
      (node (ref "X1") (pin "2") (pinfunction "R2_6_2") (pintype "passive"))
    )
    (net (code "98") (name "unconnected-(X1-R2_7-Pad3)") (class "Default")
      (node (ref "X1") (pin "3") (pinfunction "R2_7_3") (pintype "passive"))
    )
    (net (code "99") (name "unconnected-(X2-R1_5-Pad4)") (class "Default")
      (node (ref "X2") (pin "4") (pinfunction "R1_5_4") (pintype "passive"))
    )
    (net (code "100") (name "unconnected-(X2-R1_6-Pad5)") (class "Default")
      (node (ref "X2") (pin "5") (pinfunction "R1_6_5") (pintype "passive"))
    )
    (net (code "101") (name "unconnected-(X2-R1_7-Pad6)") (class "Default")
      (node (ref "X2") (pin "6") (pinfunction "R1_7_6") (pintype "passive"))
    )
    (net (code "102") (name "unconnected-(X2-R2_5-Pad1)") (class "Default")
      (node (ref "X2") (pin "1") (pinfunction "R2_5_1") (pintype "passive"))
    )
    (net (code "103") (name "unconnected-(X2-R2_6-Pad2)") (class "Default")
      (node (ref "X2") (pin "2") (pinfunction "R2_6_2") (pintype "passive"))
    )
    (net (code "104") (name "unconnected-(X2-R2_7-Pad3)") (class "Default")
      (node (ref "X2") (pin "3") (pinfunction "R2_7_3") (pintype "passive"))
    )
    (net (code "105") (name "unconnected-(X3-R1_5-Pad4)") (class "Default")
      (node (ref "X3") (pin "4") (pinfunction "R1_5_4") (pintype "passive"))
    )
    (net (code "106") (name "unconnected-(X3-R1_6-Pad5)") (class "Default")
      (node (ref "X3") (pin "5") (pinfunction "R1_6_5") (pintype "passive"))
    )
    (net (code "107") (name "unconnected-(X3-R1_7-Pad6)") (class "Default")
      (node (ref "X3") (pin "6") (pinfunction "R1_7_6") (pintype "passive"))
    )
    (net (code "108") (name "unconnected-(X3-R2_5-Pad1)") (class "Default")
      (node (ref "X3") (pin "1") (pinfunction "R2_5_1") (pintype "passive"))
    )
    (net (code "109") (name "unconnected-(X3-R2_6-Pad2)") (class "Default")
      (node (ref "X3") (pin "2") (pinfunction "R2_6_2") (pintype "passive"))
    )
    (net (code "110") (name "unconnected-(X3-R2_7-Pad3)") (class "Default")
      (node (ref "X3") (pin "3") (pinfunction "R2_7_3") (pintype "passive"))
    )
    (net (code "111") (name "unconnected-(X4-R1_5-Pad4)") (class "Default")
      (node (ref "X4") (pin "4") (pinfunction "R1_5_4") (pintype "passive"))
    )
    (net (code "112") (name "unconnected-(X4-R1_6-Pad5)") (class "Default")
      (node (ref "X4") (pin "5") (pinfunction "R1_6_5") (pintype "passive"))
    )
    (net (code "113") (name "unconnected-(X4-R1_7-Pad6)") (class "Default")
      (node (ref "X4") (pin "6") (pinfunction "R1_7_6") (pintype "passive"))
    )
    (net (code "114") (name "unconnected-(X4-R2_5-Pad1)") (class "Default")
      (node (ref "X4") (pin "1") (pinfunction "R2_5_1") (pintype "passive"))
    )
    (net (code "115") (name "unconnected-(X4-R2_6-Pad2)") (class "Default")
      (node (ref "X4") (pin "2") (pinfunction "R2_6_2") (pintype "passive"))
    )
    (net (code "116") (name "unconnected-(X4-R2_7-Pad3)") (class "Default")
      (node (ref "X4") (pin "3") (pinfunction "R2_7_3") (pintype "passive"))
    )
    (net (code "117") (name "unconnected-(X5-R1_5-Pad4)") (class "Default")
      (node (ref "X5") (pin "4") (pinfunction "R1_5_4") (pintype "passive"))
    )
    (net (code "118") (name "unconnected-(X5-R1_6-Pad5)") (class "Default")
      (node (ref "X5") (pin "5") (pinfunction "R1_6_5") (pintype "passive"))
    )
    (net (code "119") (name "unconnected-(X5-R1_7-Pad6)") (class "Default")
      (node (ref "X5") (pin "6") (pinfunction "R1_7_6") (pintype "passive"))
    )
    (net (code "120") (name "unconnected-(X5-R2_5-Pad1)") (class "Default")
      (node (ref "X5") (pin "1") (pinfunction "R2_5_1") (pintype "passive"))
    )
    (net (code "121") (name "unconnected-(X5-R2_6-Pad2)") (class "Default")
      (node (ref "X5") (pin "2") (pinfunction "R2_6_2") (pintype "passive"))
    )
    (net (code "122") (name "unconnected-(X5-R2_7-Pad3)") (class "Default")
      (node (ref "X5") (pin "3") (pinfunction "R2_7_3") (pintype "passive"))
    )
    (net (code "123") (name "unconnected-(X6-R1_5-Pad4)") (class "Default")
      (node (ref "X6") (pin "4") (pinfunction "R1_5_4") (pintype "passive"))
    )
    (net (code "124") (name "unconnected-(X6-R1_6-Pad5)") (class "Default")
      (node (ref "X6") (pin "5") (pinfunction "R1_6_5") (pintype "passive"))
    )
    (net (code "125") (name "unconnected-(X6-R1_7-Pad6)") (class "Default")
      (node (ref "X6") (pin "6") (pinfunction "R1_7_6") (pintype "passive"))
    )
    (net (code "126") (name "unconnected-(X6-R2_5-Pad1)") (class "Default")
      (node (ref "X6") (pin "1") (pinfunction "R2_5_1") (pintype "passive"))
    )
    (net (code "127") (name "unconnected-(X6-R2_6-Pad2)") (class "Default")
      (node (ref "X6") (pin "2") (pinfunction "R2_6_2") (pintype "passive"))
    )
    (net (code "128") (name "unconnected-(X6-R2_7-Pad3)") (class "Default")
      (node (ref "X6") (pin "3") (pinfunction "R2_7_3") (pintype "passive"))
    )
    (net (code "129") (name "unconnected-(X7-R1_5-Pad4)") (class "Default")
      (node (ref "X7") (pin "4") (pinfunction "R1_5_4") (pintype "passive"))
    )
    (net (code "130") (name "unconnected-(X7-R1_6-Pad5)") (class "Default")
      (node (ref "X7") (pin "5") (pinfunction "R1_6_5") (pintype "passive"))
    )
    (net (code "131") (name "unconnected-(X7-R1_7-Pad6)") (class "Default")
      (node (ref "X7") (pin "6") (pinfunction "R1_7_6") (pintype "passive"))
    )
    (net (code "132") (name "unconnected-(X7-R2_5-Pad1)") (class "Default")
      (node (ref "X7") (pin "1") (pinfunction "R2_5_1") (pintype "passive"))
    )
    (net (code "133") (name "unconnected-(X7-R2_6-Pad2)") (class "Default")
      (node (ref "X7") (pin "2") (pinfunction "R2_6_2") (pintype "passive"))
    )
    (net (code "134") (name "unconnected-(X7-R2_7-Pad3)") (class "Default")
      (node (ref "X7") (pin "3") (pinfunction "R2_7_3") (pintype "passive"))
    )
    (net (code "135") (name "unconnected-(X8-R2_5-Pad1)") (class "Default")
      (node (ref "X8") (pin "1") (pinfunction "R2_5_1") (pintype "passive"))
    )
    (net (code "136") (name "unconnected-(X8-R2_6-Pad2)") (class "Default")
      (node (ref "X8") (pin "2") (pinfunction "R2_6_2") (pintype "passive"))
    )
    (net (code "137") (name "unconnected-(X8-R2_7-Pad3)") (class "Default")
      (node (ref "X8") (pin "3") (pinfunction "R2_7_3") (pintype "passive"))
    )
    (net (code "138") (name "unconnected-(X9-+V-Pad3)") (class "Default")
      (node (ref "X9") (pin "3") (pinfunction "+V_3") (pintype "passive"))
    )
    (net (code "139") (name "unconnected-(X9--V-Pad4)") (class "Default")
      (node (ref "X9") (pin "4") (pinfunction "-V_4") (pintype "passive"))
    )
  )
)
